# UART.net
KiCad netlist of a schematic drawn in Altium Designer
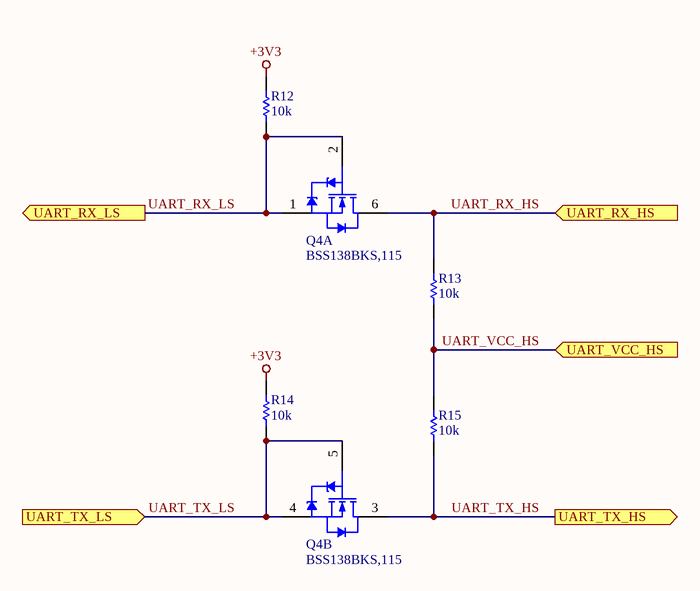
[diagram p0: UART.SchDoc]

(export (version "E")
  (design (tool "Eeschema 10.0.6"))
  (components
    (comp (ref "Q4")
      (value "BSS138BKS,115")
      (footprint "NXP-SOT363_L")
      (description "Dual N-Channel Trench MOSFET, 60 V, 0.32 A, -55 to 150 degC, 6-Pin SOT363, Tape and Reel")
      (fields (field (name "MANUFACTURER") "NXP Semiconductors"))
      (libsource (lib "Altium Content Vault") (part "NXP-NNMOS-SGDSGD-6"))
    )
    (comp (ref "R12")
      (value "10k")
      (footprint "RESC1609X55X30LL15T15")
      (description "Chip Resistor, 10 KOhm, +/- 1%, 0.1 W, -55 to 155 degC, 0603 (1608 Metric), RoHS, Tape and Reel")
      (fields (field (name "TOLERANCE") "1%") (field (name "MANUFACTURER") "Panasonic"))
      (libsource (lib "Altium Content Vault") (part "RES-2"))
    )
    (comp (ref "R13")
      (value "10k")
      (footprint "RESC1609X55X30LL15T15")
      (description "Chip Resistor, 10 KOhm, +/- 1%, 0.1 W, -55 to 155 degC, 0603 (1608 Metric), RoHS, Tape and Reel")
      (fields (field (name "TOLERANCE") "1%") (field (name "MANUFACTURER") "Panasonic"))
      (libsource (lib "Altium Content Vault") (part "RES-2"))
    )
    (comp (ref "R14")
      (value "10k")
      (footprint "RESC1609X55X30LL15T15")
      (description "Chip Resistor, 10 KOhm, +/- 1%, 0.1 W, -55 to 155 degC, 0603 (1608 Metric), RoHS, Tape and Reel")
      (fields (field (name "TOLERANCE") "1%") (field (name "MANUFACTURER") "Panasonic"))
      (libsource (lib "Altium Content Vault") (part "RES-2"))
    )
    (comp (ref "R15")
      (value "10k")
      (footprint "RESC1609X55X30LL15T15")
      (description "Chip Resistor, 10 KOhm, +/- 1%, 0.1 W, -55 to 155 degC, 0603 (1608 Metric), RoHS, Tape and Reel")
      (fields (field (name "TOLERANCE") "1%") (field (name "MANUFACTURER") "Panasonic"))
      (libsource (lib "Altium Content Vault") (part "RES-2"))
    )
  )
  (nets
    (net (code "1") (name "+3V3") (class "Default")
      (node (ref "R12") (pin "2") (pinfunction "2_2") (pintype "passive"))
      (node (ref "R14") (pin "2") (pinfunction "2_2") (pintype "passive"))
    )
    (net (code "2") (name "/UART_RX_HS") (class "Default")
      (node (ref "Q4") (pin "6") (pinfunction "D1_6") (pintype "passive"))
      (node (ref "R13") (pin "2") (pinfunction "2_2") (pintype "passive"))
    )
    (net (code "3") (name "/UART_RX_LS") (class "Default")
      (node (ref "Q4") (pin "1") (pinfunction "S1_1") (pintype "passive"))
      (node (ref "Q4") (pin "2") (pinfunction "G1_2") (pintype "passive"))
      (node (ref "R12") (pin "1") (pinfunction "1_1") (pintype "passive"))
    )
    (net (code "4") (name "/UART_TX_HS") (class "Default")
      (node (ref "Q4") (pin "3") (pinfunction "D2_3") (pintype "passive"))
      (node (ref "R15") (pin "1") (pinfunction "1_1") (pintype "passive"))
    )
    (net (code "5") (name "/UART_TX_LS") (class "Default")
      (node (ref "Q4") (pin "4") (pinfunction "S2_4") (pintype "passive"))
      (node (ref "Q4") (pin "5") (pinfunction "G2_5") (pintype "passive"))
      (node (ref "R14") (pin "1") (pinfunction "1_1") (pintype "passive"))
    )
    (net (code "6") (name "/UART_VCC_HS") (class "Default")
      (node (ref "R13") (pin "1") (pinfunction "1_1") (pintype "passive"))
      (node (ref "R15") (pin "2") (pinfunction "2_2") (pintype "passive"))
    )
  )
)
